# Main_Board_Kukang_EV.net
KiCad netlist of a schematic drawn in EAGLE
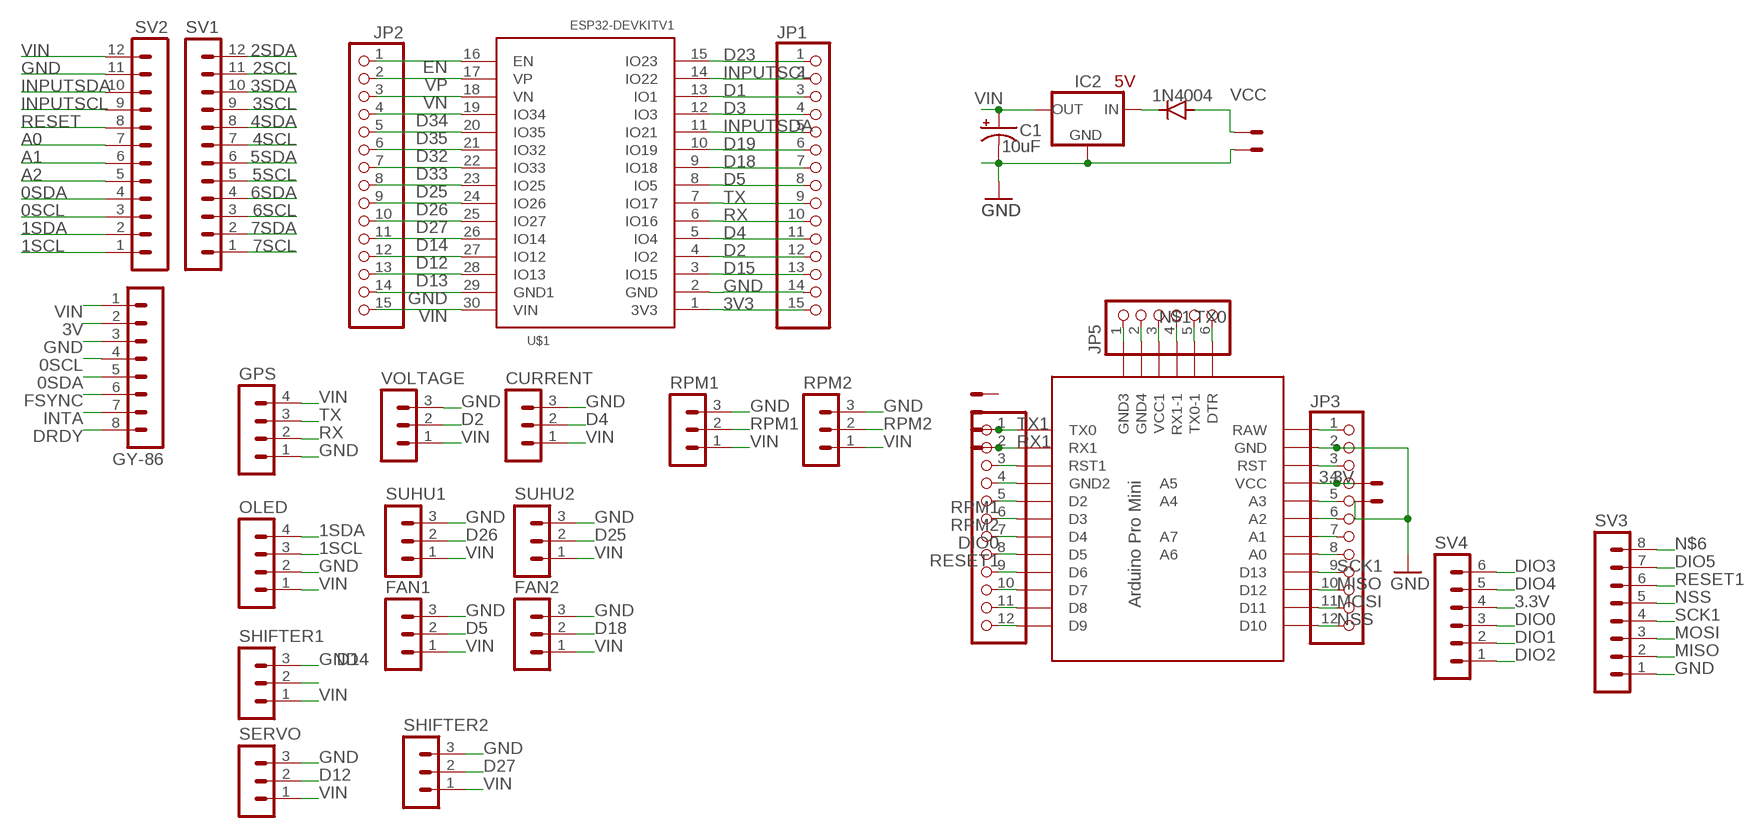
[diagram p0: schematic, sheet 1]

(export (version "E")
  (design (tool "Eeschema 10.0.6"))
  (components
    (comp (ref "C1")
      (value "10uF")
      (footprint "eagle-import:E5-10,5")
      (libsource (lib "eagle-import") (part "CPOL-USE5-10.5"))
    )
    (comp (ref "CURRENT")
      (value "MA03-1")
      (footprint "eagle-import:MA03-1")
      (libsource (lib "eagle-import") (part "MA03-1"))
    )
    (comp (ref "D1")
      (value "1N4004")
      (footprint "eagle-import:DO41-10")
      (libsource (lib "eagle-import") (part "1N4004"))
    )
    (comp (ref "ESC_BOARD")
      (value "22-23-2021")
      (footprint "eagle-import:22-23-2021")
      (fields (field (name "MF") "MOLEX"))
      (libsource (lib "eagle-import") (part "22-23-2021"))
    )
    (comp (ref "FAN1")
      (value "MA03-1")
      (footprint "eagle-import:MA03-1")
      (libsource (lib "eagle-import") (part "MA03-1"))
    )
    (comp (ref "FAN2")
      (value "MA03-1")
      (footprint "eagle-import:MA03-1")
      (libsource (lib "eagle-import") (part "MA03-1"))
    )
    (comp (ref "GPS")
      (value "MA04-1")
      (footprint "eagle-import:MA04-1")
      (libsource (lib "eagle-import") (part "MA04-1"))
    )
    (comp (ref "GY-86")
      (value "MA08-1")
      (footprint "eagle-import:MA08-1")
      (libsource (lib "eagle-import") (part "MA08-1"))
    )
    (comp (ref "IC2")
      (value "V_REG_78XX")
      (footprint "eagle-import:V78W_BACKWARDS")
      (libsource (lib "eagle-import") (part "V_REG_78XX"))
    )
    (comp (ref "JP1")
      (value "PINHD-1X15")
      (footprint "eagle-import:1X15")
      (libsource (lib "eagle-import") (part "PINHD-1X15"))
    )
    (comp (ref "JP2")
      (value "PINHD-1X15")
      (footprint "eagle-import:1X15")
      (libsource (lib "eagle-import") (part "PINHD-1X15"))
    )
    (comp (ref "JP3")
      (value "PINHD-1X12")
      (footprint "eagle-import:1X12")
      (libsource (lib "eagle-import") (part "PINHD-1X12"))
    )
    (comp (ref "JP4")
      (value "PINHD-1X12")
      (footprint "eagle-import:1X12")
      (libsource (lib "eagle-import") (part "PINHD-1X12"))
    )
    (comp (ref "JP5")
      (value "PINHD-1X6")
      (footprint "eagle-import:1X06")
      (libsource (lib "eagle-import") (part "PINHD-1X6"))
    )
    (comp (ref "OLED")
      (value "MA04-1")
      (footprint "eagle-import:MA04-1")
      (libsource (lib "eagle-import") (part "MA04-1"))
    )
    (comp (ref "POWET")
      (value "22-23-2021")
      (footprint "eagle-import:22-23-2021")
      (fields (field (name "MF") "MOLEX"))
      (libsource (lib "eagle-import") (part "22-23-2021"))
    )
    (comp (ref "RPM1")
      (value "MA03-1")
      (footprint "eagle-import:MA03-1")
      (libsource (lib "eagle-import") (part "MA03-1"))
    )
    (comp (ref "RPM2")
      (value "MA03-1")
      (footprint "eagle-import:MA03-1")
      (libsource (lib "eagle-import") (part "MA03-1"))
    )
    (comp (ref "SERVO")
      (value "MA03-1")
      (footprint "eagle-import:MA03-1")
      (libsource (lib "eagle-import") (part "MA03-1"))
    )
    (comp (ref "SHIFTER1")
      (value "MA03-1")
      (footprint "eagle-import:MA03-1")
      (libsource (lib "eagle-import") (part "MA03-1"))
    )
    (comp (ref "SHIFTER2")
      (value "MA03-1")
      (footprint "eagle-import:MA03-1")
      (libsource (lib "eagle-import") (part "MA03-1"))
    )
    (comp (ref "SUHU1")
      (value "MA03-1")
      (footprint "eagle-import:MA03-1")
      (libsource (lib "eagle-import") (part "MA03-1"))
    )
    (comp (ref "SUHU2")
      (value "MA03-1")
      (footprint "eagle-import:MA03-1")
      (libsource (lib "eagle-import") (part "MA03-1"))
    )
    (comp (ref "SV1")
      (value "MA12-1")
      (footprint "eagle-import:MA12-1")
      (libsource (lib "eagle-import") (part "MA12-1"))
    )
    (comp (ref "SV2")
      (value "MA12-1")
      (footprint "eagle-import:MA12-1")
      (libsource (lib "eagle-import") (part "MA12-1"))
    )
    (comp (ref "SV3")
      (value "MA08-1")
      (footprint "eagle-import:MA08-1")
      (libsource (lib "eagle-import") (part "MA08-1"))
    )
    (comp (ref "SV4")
      (value "MA06-1")
      (footprint "eagle-import:MA06-1")
      (libsource (lib "eagle-import") (part "MA06-1"))
    )
    (comp (ref "U$1")
      (value "ESP32DEVKITV1")
      (footprint "eagle-import:ESP32-DEVKITV1")
      (libsource (lib "eagle-import") (part "ESP32DEVKITV1"))
    )
    (comp (ref "U$2")
      (value "PRO-MINI-2")
      (footprint "eagle-import:PRO-MINI-2")
      (libsource (lib "eagle-import") (part "PRO-MINI-2"))
    )
    (comp (ref "UART_MAIN_BOARD")
      (value "22-23-2021")
      (footprint "eagle-import:22-23-2021")
      (fields (field (name "MF") "MOLEX"))
      (libsource (lib "eagle-import") (part "22-23-2021"))
    )
    (comp (ref "VBAT")
      (value "22-23-2021")
      (footprint "eagle-import:22-23-2021")
      (fields (field (name "MF") "MOLEX"))
      (libsource (lib "eagle-import") (part "22-23-2021"))
    )
    (comp (ref "VOLTAGE")
      (value "MA03-1")
      (footprint "eagle-import:MA03-1")
      (libsource (lib "eagle-import") (part "MA03-1"))
    )
  )
  (nets
    (net (code "1") (name "/0SCL") (class "Default")
      (node (ref "GY-86") (pin "4") (pinfunction "4_4") (pintype "passive"))
      (node (ref "SV2") (pin "3") (pinfunction "3_3") (pintype "passive"))
    )
    (net (code "2") (name "/0SDA") (class "Default")
      (node (ref "GY-86") (pin "5") (pinfunction "5_5") (pintype "passive"))
      (node (ref "SV2") (pin "4") (pinfunction "4_4") (pintype "passive"))
    )
    (net (code "3") (name "/1SCL") (class "Default")
      (node (ref "OLED") (pin "3") (pinfunction "3_3") (pintype "passive"))
      (node (ref "SV2") (pin "1") (pinfunction "1_1") (pintype "passive"))
    )
    (net (code "4") (name "/1SDA") (class "Default")
      (node (ref "OLED") (pin "4") (pinfunction "4_4") (pintype "passive"))
      (node (ref "SV2") (pin "2") (pinfunction "2_2") (pintype "passive"))
    )
    (net (code "5") (name "/2SCL") (class "Default")
      (node (ref "SV1") (pin "11") (pinfunction "11_11") (pintype "passive"))
    )
    (net (code "6") (name "/2SDA") (class "Default")
      (node (ref "SV1") (pin "12") (pinfunction "12_12") (pintype "passive"))
    )
    (net (code "7") (name "/3.3V") (class "Default")
      (node (ref "JP3") (pin "4") (pinfunction "4_4") (pintype "passive"))
      (node (ref "POWET") (pin "1") (pinfunction "S_1") (pintype "passive"))
      (node (ref "SV4") (pin "4") (pinfunction "4_4") (pintype "passive"))
      (node (ref "U$2") (pin "VCC") (pinfunction "VCC_VCC") (pintype "bidirectional"))
    )
    (net (code "8") (name "/3SCL") (class "Default")
      (node (ref "SV1") (pin "9") (pinfunction "9_9") (pintype "passive"))
    )
    (net (code "9") (name "/3SDA") (class "Default")
      (node (ref "SV1") (pin "10") (pinfunction "10_10") (pintype "passive"))
    )
    (net (code "10") (name "/3V") (class "Default")
      (node (ref "GY-86") (pin "2") (pinfunction "2_2") (pintype "passive"))
    )
    (net (code "11") (name "/3V3") (class "Default")
      (node (ref "JP1") (pin "15") (pinfunction "15_15") (pintype "passive"))
      (node (ref "U$1") (pin "1") (pinfunction "3V3_1") (pintype "bidirectional"))
    )
    (net (code "12") (name "/4SCL") (class "Default")
      (node (ref "SV1") (pin "7") (pinfunction "7_7") (pintype "passive"))
    )
    (net (code "13") (name "/4SDA") (class "Default")
      (node (ref "SV1") (pin "8") (pinfunction "8_8") (pintype "passive"))
    )
    (net (code "14") (name "/5SCL") (class "Default")
      (node (ref "SV1") (pin "5") (pinfunction "5_5") (pintype "passive"))
    )
    (net (code "15") (name "/5SDA") (class "Default")
      (node (ref "SV1") (pin "6") (pinfunction "6_6") (pintype "passive"))
    )
    (net (code "16") (name "/6SCL") (class "Default")
      (node (ref "SV1") (pin "3") (pinfunction "3_3") (pintype "passive"))
    )
    (net (code "17") (name "/6SDA") (class "Default")
      (node (ref "SV1") (pin "4") (pinfunction "4_4") (pintype "passive"))
    )
    (net (code "18") (name "/7SCL") (class "Default")
      (node (ref "SV1") (pin "1") (pinfunction "1_1") (pintype "passive"))
    )
    (net (code "19") (name "/7SDA") (class "Default")
      (node (ref "SV1") (pin "2") (pinfunction "2_2") (pintype "passive"))
    )
    (net (code "20") (name "/A0") (class "Default")
      (node (ref "SV2") (pin "7") (pinfunction "7_7") (pintype "passive"))
    )
    (net (code "21") (name "/A1") (class "Default")
      (node (ref "SV2") (pin "6") (pinfunction "6_6") (pintype "passive"))
    )
    (net (code "22") (name "/A2") (class "Default")
      (node (ref "SV2") (pin "5") (pinfunction "5_5") (pintype "passive"))
    )
    (net (code "23") (name "/D1") (class "Default")
      (node (ref "JP1") (pin "3") (pinfunction "3_3") (pintype "passive"))
      (node (ref "U$1") (pin "13") (pinfunction "IO1_13") (pintype "bidirectional"))
    )
    (net (code "24") (name "/D2") (class "Default")
      (node (ref "JP1") (pin "12") (pinfunction "12_12") (pintype "passive"))
      (node (ref "U$1") (pin "4") (pinfunction "IO2_4") (pintype "bidirectional"))
      (node (ref "VOLTAGE") (pin "2") (pinfunction "2_2") (pintype "passive"))
    )
    (net (code "25") (name "/D3") (class "Default")
      (node (ref "JP1") (pin "4") (pinfunction "4_4") (pintype "passive"))
      (node (ref "U$1") (pin "12") (pinfunction "IO3_12") (pintype "bidirectional"))
    )
    (net (code "26") (name "/D4") (class "Default")
      (node (ref "CURRENT") (pin "2") (pinfunction "2_2") (pintype "passive"))
      (node (ref "JP1") (pin "11") (pinfunction "11_11") (pintype "passive"))
      (node (ref "U$1") (pin "5") (pinfunction "IO4_5") (pintype "bidirectional"))
    )
    (net (code "27") (name "/D5") (class "Default")
      (node (ref "FAN1") (pin "2") (pinfunction "2_2") (pintype "passive"))
      (node (ref "JP1") (pin "8") (pinfunction "8_8") (pintype "passive"))
      (node (ref "U$1") (pin "8") (pinfunction "IO5_8") (pintype "bidirectional"))
    )
    (net (code "28") (name "/D12") (class "Default")
      (node (ref "JP2") (pin "12") (pinfunction "12_12") (pintype "passive"))
      (node (ref "SERVO") (pin "2") (pinfunction "2_2") (pintype "passive"))
      (node (ref "U$1") (pin "27") (pinfunction "IO12_27") (pintype "bidirectional"))
    )
    (net (code "29") (name "/D13") (class "Default")
      (node (ref "JP2") (pin "13") (pinfunction "13_13") (pintype "passive"))
      (node (ref "U$1") (pin "28") (pinfunction "IO13_28") (pintype "bidirectional"))
    )
    (net (code "30") (name "/D14") (class "Default")
      (node (ref "JP2") (pin "11") (pinfunction "11_11") (pintype "passive"))
      (node (ref "SHIFTER1") (pin "2") (pinfunction "2_2") (pintype "passive"))
      (node (ref "U$1") (pin "26") (pinfunction "IO14_26") (pintype "bidirectional"))
    )
    (net (code "31") (name "/D15") (class "Default")
      (node (ref "JP1") (pin "13") (pinfunction "13_13") (pintype "passive"))
      (node (ref "U$1") (pin "3") (pinfunction "IO15_3") (pintype "bidirectional"))
    )
    (net (code "32") (name "/D18") (class "Default")
      (node (ref "FAN2") (pin "2") (pinfunction "2_2") (pintype "passive"))
      (node (ref "JP1") (pin "7") (pinfunction "7_7") (pintype "passive"))
      (node (ref "U$1") (pin "9") (pinfunction "IO18_9") (pintype "bidirectional"))
    )
    (net (code "33") (name "/D19") (class "Default")
      (node (ref "JP1") (pin "6") (pinfunction "6_6") (pintype "passive"))
      (node (ref "U$1") (pin "10") (pinfunction "IO19_10") (pintype "bidirectional"))
    )
    (net (code "34") (name "/D23") (class "Default")
      (node (ref "JP1") (pin "1") (pinfunction "1_1") (pintype "passive"))
      (node (ref "U$1") (pin "15") (pinfunction "IO23_15") (pintype "bidirectional"))
    )
    (net (code "35") (name "/D25") (class "Default")
      (node (ref "JP2") (pin "8") (pinfunction "8_8") (pintype "passive"))
      (node (ref "SUHU2") (pin "2") (pinfunction "2_2") (pintype "passive"))
      (node (ref "U$1") (pin "23") (pinfunction "IO25_23") (pintype "bidirectional"))
    )
    (net (code "36") (name "/D26") (class "Default")
      (node (ref "JP2") (pin "9") (pinfunction "9_9") (pintype "passive"))
      (node (ref "SUHU1") (pin "2") (pinfunction "2_2") (pintype "passive"))
      (node (ref "U$1") (pin "24") (pinfunction "IO26_24") (pintype "bidirectional"))
    )
    (net (code "37") (name "/D27") (class "Default")
      (node (ref "JP2") (pin "10") (pinfunction "10_10") (pintype "passive"))
      (node (ref "SHIFTER2") (pin "2") (pinfunction "2_2") (pintype "passive"))
      (node (ref "U$1") (pin "25") (pinfunction "IO27_25") (pintype "bidirectional"))
    )
    (net (code "38") (name "/D32") (class "Default")
      (node (ref "JP2") (pin "6") (pinfunction "6_6") (pintype "passive"))
      (node (ref "U$1") (pin "21") (pinfunction "IO32_21") (pintype "bidirectional"))
    )
    (net (code "39") (name "/D33") (class "Default")
      (node (ref "JP2") (pin "7") (pinfunction "7_7") (pintype "passive"))
      (node (ref "U$1") (pin "22") (pinfunction "IO33_22") (pintype "bidirectional"))
    )
    (net (code "40") (name "/D34") (class "Default")
      (node (ref "JP2") (pin "4") (pinfunction "4_4") (pintype "passive"))
      (node (ref "U$1") (pin "19") (pinfunction "IO34_19") (pintype "bidirectional"))
    )
    (net (code "41") (name "/D35") (class "Default")
      (node (ref "JP2") (pin "5") (pinfunction "5_5") (pintype "passive"))
      (node (ref "U$1") (pin "20") (pinfunction "IO35_20") (pintype "bidirectional"))
    )
    (net (code "42") (name "/DIO0") (class "Default")
      (node (ref "JP4") (pin "7") (pinfunction "7_7") (pintype "passive"))
      (node (ref "SV4") (pin "3") (pinfunction "3_3") (pintype "passive"))
      (node (ref "U$2") (pin "D4") (pinfunction "D4_D4") (pintype "bidirectional"))
    )
    (net (code "43") (name "/DIO1") (class "Default")
      (node (ref "JP4") (pin "9") (pinfunction "9_9") (pintype "passive"))
      (node (ref "SV4") (pin "2") (pinfunction "2_2") (pintype "passive"))
      (node (ref "U$2") (pin "D6") (pinfunction "D6_D6") (pintype "bidirectional"))
    )
    (net (code "44") (name "/DIO2") (class "Default")
      (node (ref "SV4") (pin "1") (pinfunction "1_1") (pintype "passive"))
    )
    (net (code "45") (name "/DIO3") (class "Default")
      (node (ref "SV4") (pin "6") (pinfunction "6_6") (pintype "passive"))
    )
    (net (code "46") (name "/DIO4") (class "Default")
      (node (ref "SV4") (pin "5") (pinfunction "5_5") (pintype "passive"))
    )
    (net (code "47") (name "/DIO5") (class "Default")
      (node (ref "SV3") (pin "7") (pinfunction "7_7") (pintype "passive"))
    )
    (net (code "48") (name "/DRDY") (class "Default")
      (node (ref "GY-86") (pin "8") (pinfunction "8_8") (pintype "passive"))
    )
    (net (code "49") (name "/EN") (class "Default")
      (node (ref "JP2") (pin "1") (pinfunction "1_1") (pintype "passive"))
      (node (ref "U$1") (pin "16") (pinfunction "EN_16") (pintype "bidirectional"))
    )
    (net (code "50") (name "/FSYNC") (class "Default")
      (node (ref "GY-86") (pin "6") (pinfunction "6_6") (pintype "passive"))
    )
    (net (code "51") (name "/INPUTSCL") (class "Default")
      (node (ref "JP1") (pin "2") (pinfunction "2_2") (pintype "passive"))
      (node (ref "SV2") (pin "9") (pinfunction "9_9") (pintype "passive"))
      (node (ref "U$1") (pin "14") (pinfunction "IO22_14") (pintype "bidirectional"))
    )
    (net (code "52") (name "/INPUTSDA") (class "Default")
      (node (ref "JP1") (pin "5") (pinfunction "5_5") (pintype "passive"))
      (node (ref "SV2") (pin "10") (pinfunction "10_10") (pintype "passive"))
      (node (ref "U$1") (pin "11") (pinfunction "IO21_11") (pintype "bidirectional"))
    )
    (net (code "53") (name "/INTA") (class "Default")
      (node (ref "GY-86") (pin "7") (pinfunction "7_7") (pintype "passive"))
    )
    (net (code "54") (name "/MISO") (class "Default")
      (node (ref "JP3") (pin "10") (pinfunction "10_10") (pintype "passive"))
      (node (ref "SV3") (pin "2") (pinfunction "2_2") (pintype "passive"))
      (node (ref "U$2") (pin "D12") (pinfunction "D12_D12") (pintype "bidirectional"))
    )
    (net (code "55") (name "/MOSI") (class "Default")
      (node (ref "JP3") (pin "11") (pinfunction "11_11") (pintype "passive"))
      (node (ref "SV3") (pin "3") (pinfunction "3_3") (pintype "passive"))
      (node (ref "U$2") (pin "D11") (pinfunction "D11_D11") (pintype "bidirectional"))
    )
    (net (code "56") (name "/N$1") (class "Default")
      (node (ref "JP5") (pin "3") (pinfunction "3_3") (pintype "passive"))
      (node (ref "U$2") (pin "VCC1") (pinfunction "VCC1_VCC1") (pintype "bidirectional"))
    )
    (net (code "57") (name "/N$6") (class "Default")
      (node (ref "SV3") (pin "8") (pinfunction "8_8") (pintype "passive"))
    )
    (net (code "58") (name "/NSS") (class "Default")
      (node (ref "JP3") (pin "12") (pinfunction "12_12") (pintype "passive"))
      (node (ref "SV3") (pin "5") (pinfunction "5_5") (pintype "passive"))
      (node (ref "U$2") (pin "D10") (pinfunction "D10_D10") (pintype "bidirectional"))
    )
    (net (code "59") (name "/RESET") (class "Default")
      (node (ref "SV2") (pin "8") (pinfunction "8_8") (pintype "passive"))
    )
    (net (code "60") (name "/RESET1") (class "Default")
      (node (ref "JP4") (pin "8") (pinfunction "8_8") (pintype "passive"))
      (node (ref "SV3") (pin "6") (pinfunction "6_6") (pintype "passive"))
      (node (ref "U$2") (pin "D5") (pinfunction "D5_D5") (pintype "bidirectional"))
    )
    (net (code "61") (name "/RPM1") (class "Default")
      (node (ref "JP4") (pin "5") (pinfunction "5_5") (pintype "passive"))
      (node (ref "RPM1") (pin "2") (pinfunction "2_2") (pintype "passive"))
      (node (ref "U$2") (pin "D2") (pinfunction "D2_D2") (pintype "bidirectional"))
    )
    (net (code "62") (name "/RPM2") (class "Default")
      (node (ref "JP4") (pin "6") (pinfunction "6_6") (pintype "passive"))
      (node (ref "RPM2") (pin "2") (pinfunction "2_2") (pintype "passive"))
      (node (ref "U$2") (pin "D3") (pinfunction "D3_D3") (pintype "bidirectional"))
    )
    (net (code "63") (name "/RX") (class "Default")
      (node (ref "GPS") (pin "2") (pinfunction "2_2") (pintype "passive"))
      (node (ref "JP1") (pin "10") (pinfunction "10_10") (pintype "passive"))
      (node (ref "U$1") (pin "6") (pinfunction "IO16_6") (pintype "bidirectional"))
    )
    (net (code "64") (name "/RX1") (class "Default")
      (node (ref "JP4") (pin "2") (pinfunction "2_2") (pintype "passive"))
      (node (ref "U$2") (pin "RX1") (pinfunction "RX1_RX1") (pintype "bidirectional"))
      (node (ref "UART_MAIN_BOARD") (pin "2") (pinfunction "S_2") (pintype "passive"))
    )
    (net (code "65") (name "/SCK1") (class "Default")
      (node (ref "JP3") (pin "9") (pinfunction "9_9") (pintype "passive"))
      (node (ref "SV3") (pin "4") (pinfunction "4_4") (pintype "passive"))
      (node (ref "U$2") (pin "D13") (pinfunction "D13_D13") (pintype "bidirectional"))
    )
    (net (code "66") (name "/TX") (class "Default")
      (node (ref "GPS") (pin "3") (pinfunction "3_3") (pintype "passive"))
      (node (ref "JP1") (pin "9") (pinfunction "9_9") (pintype "passive"))
      (node (ref "U$1") (pin "7") (pinfunction "IO17_7") (pintype "bidirectional"))
    )
    (net (code "67") (name "/TX0") (class "Default")
      (node (ref "JP5") (pin "5") (pinfunction "5_5") (pintype "passive"))
      (node (ref "U$2") (pin "TX0-1") (pinfunction "TX0-1_TX0-1") (pintype "bidirectional"))
    )
    (net (code "68") (name "/TX1") (class "Default")
      (node (ref "JP4") (pin "1") (pinfunction "1_1") (pintype "passive"))
      (node (ref "U$2") (pin "TX0") (pinfunction "TX0_TX0") (pintype "bidirectional"))
      (node (ref "UART_MAIN_BOARD") (pin "1") (pinfunction "S_1") (pintype "passive"))
    )
    (net (code "69") (name "/VCC") (class "Default")
      (node (ref "D1") (pin "A") (pinfunction "A_A") (pintype "passive"))
      (node (ref "VBAT") (pin "1") (pinfunction "S_1") (pintype "passive"))
    )
    (net (code "70") (name "/VIN") (class "Default")
      (node (ref "C1") (pin "+") (pinfunction "+_+") (pintype "passive"))
      (node (ref "CURRENT") (pin "1") (pinfunction "1_1") (pintype "passive"))
      (node (ref "FAN1") (pin "1") (pinfunction "1_1") (pintype "passive"))
      (node (ref "FAN2") (pin "1") (pinfunction "1_1") (pintype "passive"))
      (node (ref "GPS") (pin "4") (pinfunction "4_4") (pintype "passive"))
      (node (ref "GY-86") (pin "1") (pinfunction "1_1") (pintype "passive"))
      (node (ref "IC2") (pin "OUT") (pinfunction "OUT_OUT") (pintype "output"))
      (node (ref "JP2") (pin "15") (pinfunction "15_15") (pintype "passive"))
      (node (ref "OLED") (pin "1") (pinfunction "1_1") (pintype "passive"))
      (node (ref "RPM1") (pin "1") (pinfunction "1_1") (pintype "passive"))
      (node (ref "RPM2") (pin "1") (pinfunction "1_1") (pintype "passive"))
      (node (ref "SERVO") (pin "1") (pinfunction "1_1") (pintype "passive"))
      (node (ref "SHIFTER1") (pin "1") (pinfunction "1_1") (pintype "passive"))
      (node (ref "SHIFTER2") (pin "1") (pinfunction "1_1") (pintype "passive"))
      (node (ref "SUHU1") (pin "1") (pinfunction "1_1") (pintype "passive"))
      (node (ref "SUHU2") (pin "1") (pinfunction "1_1") (pintype "passive"))
      (node (ref "SV2") (pin "12") (pinfunction "12_12") (pintype "passive"))
      (node (ref "U$1") (pin "30") (pinfunction "VIN_30") (pintype "bidirectional"))
      (node (ref "VOLTAGE") (pin "1") (pinfunction "1_1") (pintype "passive"))
    )
    (net (code "71") (name "/VN") (class "Default")
      (node (ref "JP2") (pin "3") (pinfunction "3_3") (pintype "passive"))
      (node (ref "U$1") (pin "18") (pinfunction "VN_18") (pintype "bidirectional"))
    )
    (net (code "72") (name "/VP") (class "Default")
      (node (ref "JP2") (pin "2") (pinfunction "2_2") (pintype "passive"))
      (node (ref "U$1") (pin "17") (pinfunction "VP_17") (pintype "bidirectional"))
    )
    (net (code "73") (name "GND") (class "Default")
      (node (ref "C1") (pin "-") (pinfunction "-_-") (pintype "passive"))
      (node (ref "CURRENT") (pin "3") (pinfunction "3_3") (pintype "passive"))
      (node (ref "FAN1") (pin "3") (pinfunction "3_3") (pintype "passive"))
      (node (ref "FAN2") (pin "3") (pinfunction "3_3") (pintype "passive"))
      (node (ref "GPS") (pin "1") (pinfunction "1_1") (pintype "passive"))
      (node (ref "GY-86") (pin "3") (pinfunction "3_3") (pintype "passive"))
      (node (ref "IC2") (pin "GND") (pinfunction "GND_GND") (pintype "input"))
      (node (ref "JP1") (pin "14") (pinfunction "14_14") (pintype "passive"))
      (node (ref "JP2") (pin "14") (pinfunction "14_14") (pintype "passive"))
      (node (ref "JP3") (pin "2") (pinfunction "2_2") (pintype "passive"))
      (node (ref "OLED") (pin "2") (pinfunction "2_2") (pintype "passive"))
      (node (ref "POWET") (pin "2") (pinfunction "S_2") (pintype "passive"))
      (node (ref "RPM1") (pin "3") (pinfunction "3_3") (pintype "passive"))
      (node (ref "RPM2") (pin "3") (pinfunction "3_3") (pintype "passive"))
      (node (ref "SERVO") (pin "3") (pinfunction "3_3") (pintype "passive"))
      (node (ref "SHIFTER1") (pin "3") (pinfunction "3_3") (pintype "passive"))
      (node (ref "SHIFTER2") (pin "3") (pinfunction "3_3") (pintype "passive"))
      (node (ref "SUHU1") (pin "3") (pinfunction "3_3") (pintype "passive"))
      (node (ref "SUHU2") (pin "3") (pinfunction "3_3") (pintype "passive"))
      (node (ref "SV2") (pin "11") (pinfunction "11_11") (pintype "passive"))
      (node (ref "SV3") (pin "1") (pinfunction "1_1") (pintype "passive"))
      (node (ref "U$1") (pin "2") (pinfunction "GND_2") (pintype "bidirectional"))
      (node (ref "U$1") (pin "29") (pinfunction "GND1_29") (pintype "bidirectional"))
      (node (ref "U$2") (pin "GND") (pinfunction "GND_GND") (pintype "bidirectional"))
      (node (ref "VBAT") (pin "2") (pinfunction "S_2") (pintype "passive"))
      (node (ref "VOLTAGE") (pin "3") (pinfunction "3_3") (pintype "passive"))
    )
    (net (code "74") (name "Net-(D1-PadC)") (class "Default")
      (node (ref "D1") (pin "C") (pinfunction "C_C") (pintype "passive"))
      (node (ref "IC2") (pin "IN") (pinfunction "IN_IN") (pintype "input"))
    )
    (net (code "75") (name "Net-(JP3-Pad1)") (class "Default")
      (node (ref "JP3") (pin "1") (pinfunction "1_1") (pintype "passive"))
      (node (ref "U$2") (pin "RAW") (pinfunction "RAW_RAW") (pintype "bidirectional"))
    )
    (net (code "76") (name "Net-(JP3-Pad3)") (class "Default")
      (node (ref "JP3") (pin "3") (pinfunction "3_3") (pintype "passive"))
      (node (ref "U$2") (pin "RST") (pinfunction "RST_RST") (pintype "bidirectional"))
    )
    (net (code "77") (name "Net-(JP3-Pad5)") (class "Default")
      (node (ref "JP3") (pin "5") (pinfunction "5_5") (pintype "passive"))
      (node (ref "U$2") (pin "A3") (pinfunction "A3_A3") (pintype "bidirectional"))
    )
    (net (code "78") (name "Net-(JP3-Pad6)") (class "Default")
      (node (ref "JP3") (pin "6") (pinfunction "6_6") (pintype "passive"))
      (node (ref "U$2") (pin "A2") (pinfunction "A2_A2") (pintype "bidirectional"))
    )
    (net (code "79") (name "Net-(JP3-Pad7)") (class "Default")
      (node (ref "JP3") (pin "7") (pinfunction "7_7") (pintype "passive"))
      (node (ref "U$2") (pin "A1") (pinfunction "A1_A1") (pintype "bidirectional"))
    )
    (net (code "80") (name "Net-(JP3-Pad8)") (class "Default")
      (node (ref "JP3") (pin "8") (pinfunction "8_8") (pintype "passive"))
      (node (ref "U$2") (pin "A0") (pinfunction "A0_A0") (pintype "bidirectional"))
    )
    (net (code "81") (name "Net-(JP4-Pad3)") (class "Default")
      (node (ref "JP4") (pin "3") (pinfunction "3_3") (pintype "passive"))
      (node (ref "U$2") (pin "RST1") (pinfunction "RST1_RST1") (pintype "bidirectional"))
    )
    (net (code "82") (name "Net-(JP4-Pad10)") (class "Default")
      (node (ref "JP4") (pin "10") (pinfunction "10_10") (pintype "passive"))
      (node (ref "U$2") (pin "D7") (pinfunction "D7_D7") (pintype "bidirectional"))
    )
    (net (code "83") (name "Net-(JP4-Pad11)") (class "Default")
      (node (ref "JP4") (pin "11") (pinfunction "11_11") (pintype "passive"))
      (node (ref "U$2") (pin "D8") (pinfunction "D8_D8") (pintype "bidirectional"))
    )
    (net (code "84") (name "Net-(JP4-Pad12)") (class "Default")
      (node (ref "JP4") (pin "12") (pinfunction "12_12") (pintype "passive"))
      (node (ref "U$2") (pin "D9") (pinfunction "D9_D9") (pintype "bidirectional"))
    )
    (net (code "85") (name "Net-(JP5-Pad4)") (class "Default")
      (node (ref "JP5") (pin "4") (pinfunction "4_4") (pintype "passive"))
      (node (ref "U$2") (pin "RX1-1") (pinfunction "RX1-1_RX1-1") (pintype "bidirectional"))
    )
    (net (code "86") (name "Net-(JP5-Pad6)") (class "Default")
      (node (ref "JP5") (pin "6") (pinfunction "6_6") (pintype "passive"))
      (node (ref "U$2") (pin "DTR") (pinfunction "DTR_DTR") (pintype "bidirectional"))
    )
    (net (code "87") (name "Net-(U$2-GND2)") (class "Default")
      (node (ref "JP4") (pin "4") (pinfunction "4_4") (pintype "passive"))
      (node (ref "U$2") (pin "GND1") (pinfunction "GND2_GND1") (pintype "bidirectional"))
    )
    (net (code "88") (name "Net-(U$2-GND3)") (class "Default")
      (node (ref "JP5") (pin "1") (pinfunction "1_1") (pintype "passive"))
      (node (ref "U$2") (pin "GND2") (pinfunction "GND3_GND2") (pintype "bidirectional"))
    )
    (net (code "89") (name "Net-(U$2-GND4)") (class "Default")
      (node (ref "JP5") (pin "2") (pinfunction "2_2") (pintype "passive"))
      (node (ref "U$2") (pin "GND3") (pinfunction "GND4_GND3") (pintype "bidirectional"))
    )
    (net (code "90") (name "unconnected-(ESC_BOARDA-S-Pad1)") (class "Default")
      (node (ref "ESC_BOARD") (pin "1") (pinfunction "S_1") (pintype "passive"))
    )
    (net (code "91") (name "unconnected-(ESC_BOARDB-S-Pad2)") (class "Default")
      (node (ref "ESC_BOARD") (pin "2") (pinfunction "S_2") (pintype "passive"))
    )
    (net (code "92") (name "unconnected-(U$2-PadA4)") (class "Default")
      (node (ref "U$2") (pin "A4") (pinfunction "A4_A4") (pintype "bidirectional"))
    )
    (net (code "93") (name "unconnected-(U$2-PadA5)") (class "Default")
      (node (ref "U$2") (pin "A5") (pinfunction "A5_A5") (pintype "bidirectional"))
    )
    (net (code "94") (name "unconnected-(U$2-PadA6)") (class "Default")
      (node (ref "U$2") (pin "A6") (pinfunction "A6_A6") (pintype "bidirectional"))
    )
    (net (code "95") (name "unconnected-(U$2-PadA7)") (class "Default")
      (node (ref "U$2") (pin "A7") (pinfunction "A7_A7") (pintype "bidirectional"))
    )
  )
)
